# openEMSstim_02.net
KiCad netlist of a schematic drawn in EAGLE
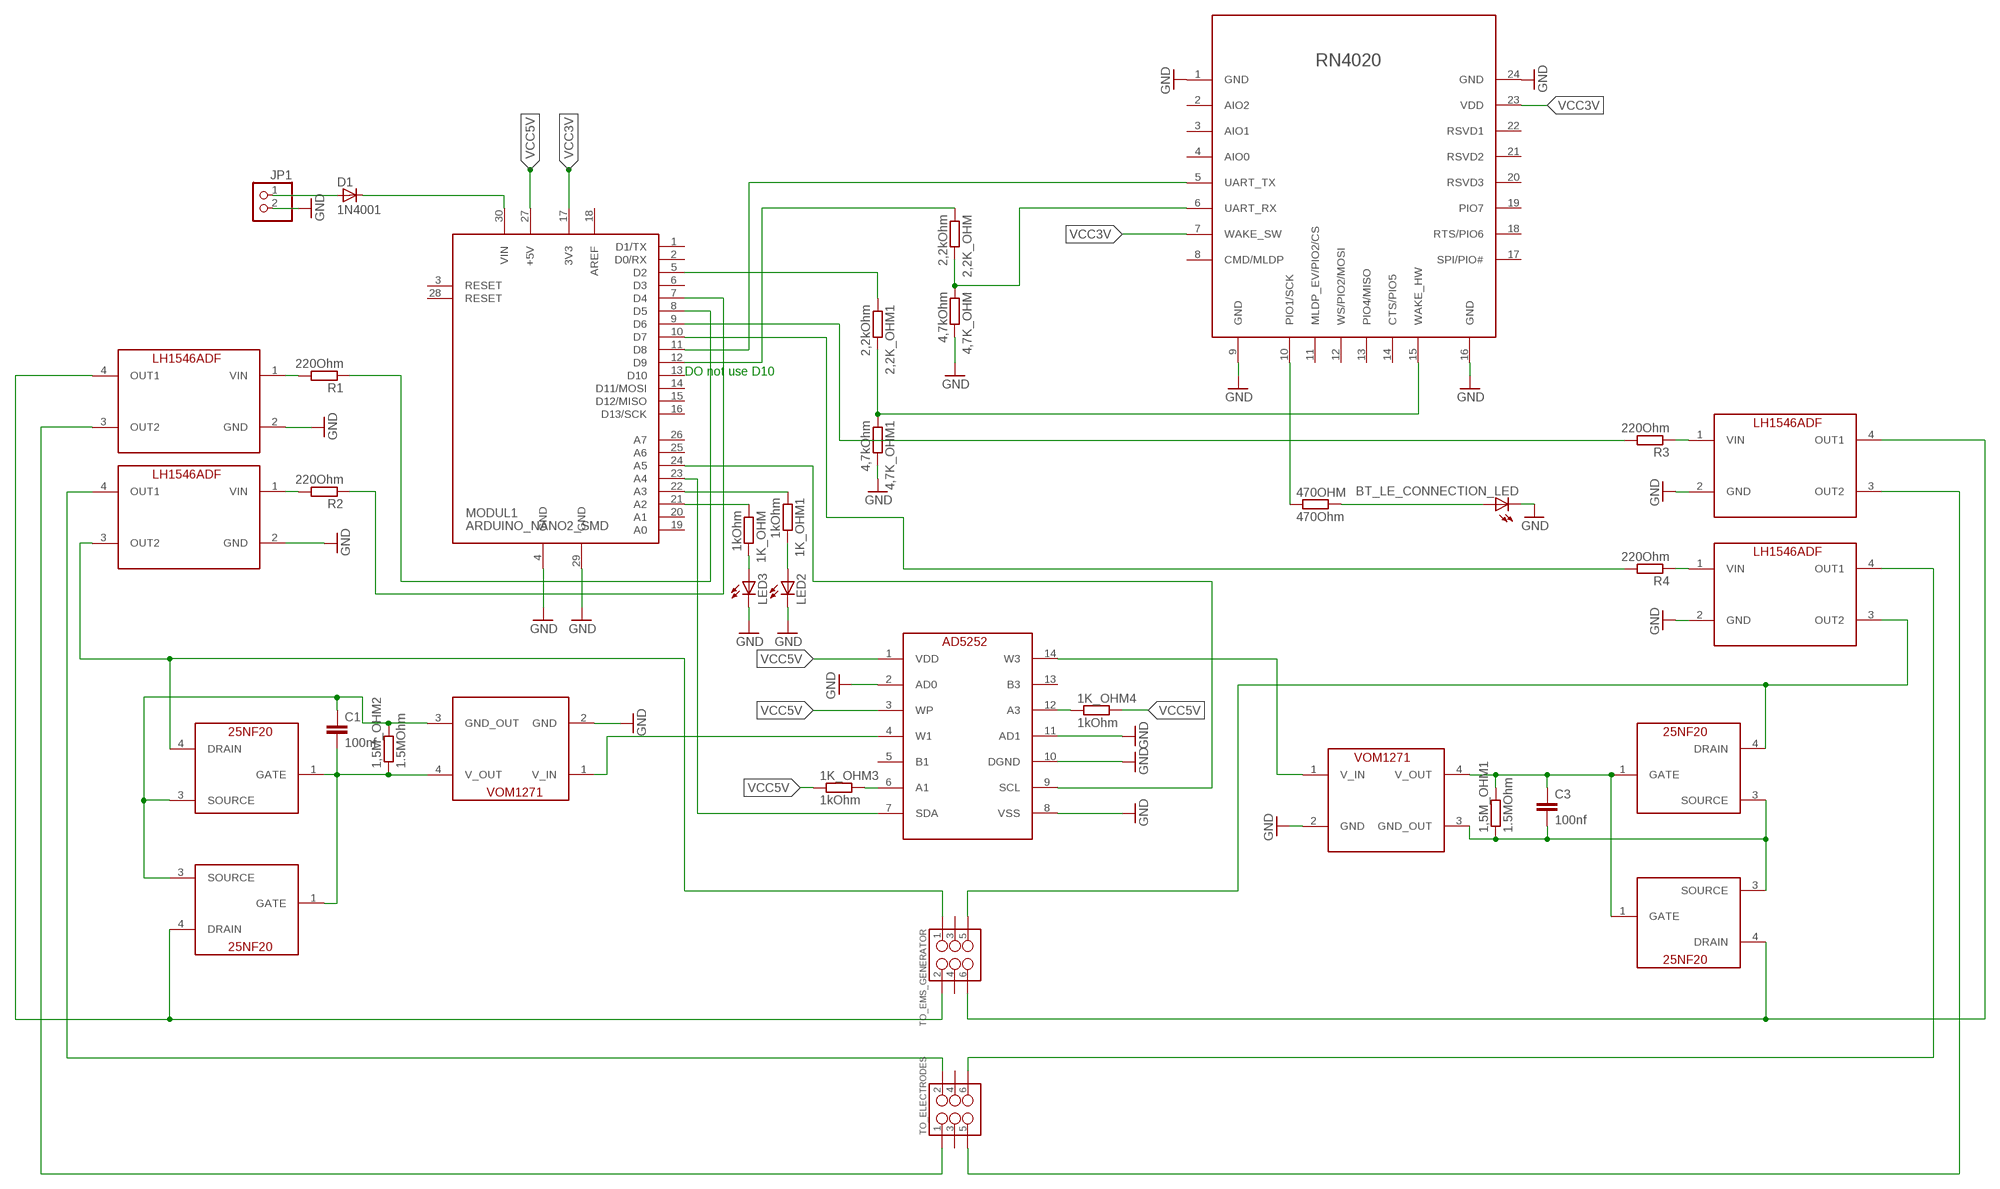
[diagram p0: schematic, sheet 1]

(export (version "E")
  (design (tool "Eeschema 10.0.6"))
  (components
    (comp (ref "1,5M_OHM1")
      (value "1.5MOhm")
      (footprint "eagle-import:R0805")
      (libsource (lib "eagle-import") (part "R-EU_R0805"))
    )
    (comp (ref "1,5M_OHM2")
      (value "1.5MOhm")
      (footprint "eagle-import:R0805")
      (libsource (lib "eagle-import") (part "R-EU_R0805"))
    )
    (comp (ref "1K_OHM")
      (value "1kOhm")
      (footprint "eagle-import:R0805")
      (libsource (lib "eagle-import") (part "R-EU_R0805"))
    )
    (comp (ref "1K_OHM1")
      (value "1kOhm")
      (footprint "eagle-import:R0805")
      (libsource (lib "eagle-import") (part "R-EU_R0805"))
    )
    (comp (ref "1K_OHM3")
      (value "1kOhm")
      (footprint "eagle-import:R0805")
      (libsource (lib "eagle-import") (part "R-EU_R0805"))
    )
    (comp (ref "1K_OHM4")
      (value "1kOhm")
      (footprint "eagle-import:R0805")
      (libsource (lib "eagle-import") (part "R-EU_R0805"))
    )
    (comp (ref "2,2K_OHM")
      (value "2,2kOhm")
      (footprint "eagle-import:R0805")
      (libsource (lib "eagle-import") (part "R-EU_R0805"))
    )
    (comp (ref "2,2K_OHM1")
      (value "2,2kOhm")
      (footprint "eagle-import:R0805")
      (libsource (lib "eagle-import") (part "R-EU_R0805"))
    )
    (comp (ref "4,7K_OHM")
      (value "4,7kOhm")
      (footprint "eagle-import:R0805")
      (libsource (lib "eagle-import") (part "R-EU_R0805"))
    )
    (comp (ref "4,7K_OHM1")
      (value "4,7kOhm")
      (footprint "eagle-import:R0805")
      (libsource (lib "eagle-import") (part "R-EU_R0805"))
    )
    (comp (ref "470OHM")
      (value "470Ohm")
      (footprint "eagle-import:R0805")
      (libsource (lib "eagle-import") (part "R-EU_R0805"))
    )
    (comp (ref "BT_LE_CONNECTION_LED")
      (value "LEDCHIPLED_0603")
      (footprint "eagle-import:CHIPLED_0603")
      (libsource (lib "eagle-import") (part "LEDCHIPLED_0603"))
    )
    (comp (ref "C1")
      (value "100nf")
      (footprint "eagle-import:0805")
      (libsource (lib "eagle-import") (part "CAP0805"))
    )
    (comp (ref "C3")
      (value "100nf")
      (footprint "eagle-import:0805")
      (libsource (lib "eagle-import") (part "CAP0805"))
    )
    (comp (ref "D1")
      (value "1N4001")
      (footprint "eagle-import:SMB")
      (libsource (lib "eagle-import") (part "D-SMB"))
    )
    (comp (ref "JP1")
      (value "PINHD-1X2")
      (footprint "eagle-import:1X02")
      (libsource (lib "eagle-import") (part "PINHD-1X2"))
    )
    (comp (ref "LED2")
      (value "LEDCHIPLED_0603")
      (footprint "eagle-import:CHIPLED_0603")
      (libsource (lib "eagle-import") (part "LEDCHIPLED_0603"))
    )
    (comp (ref "LED3")
      (value "LEDCHIPLED_0603")
      (footprint "eagle-import:CHIPLED_0603")
      (libsource (lib "eagle-import") (part "LEDCHIPLED_0603"))
    )
    (comp (ref "MODUL1")
      (value "ARDUINO_NANO2_SMD")
      (footprint "eagle-import:ARDUINO_NANO2_SMD")
      (libsource (lib "eagle-import") (part "ARDUINO_NANO2_SMD"))
    )
    (comp (ref "MOS01")
      (value "DEV")
      (footprint "eagle-import:PACK")
      (libsource (lib "eagle-import") (part "DEV"))
    )
    (comp (ref "MOS02")
      (value "DEV")
      (footprint "eagle-import:PACK")
      (libsource (lib "eagle-import") (part "DEV"))
    )
    (comp (ref "MOS03")
      (value "DEV")
      (footprint "eagle-import:PACK")
      (libsource (lib "eagle-import") (part "DEV"))
    )
    (comp (ref "MOS04")
      (value "DEV")
      (footprint "eagle-import:PACK")
      (libsource (lib "eagle-import") (part "DEV"))
    )
    (comp (ref "R1")
      (value "220Ohm")
      (footprint "eagle-import:R0805")
      (libsource (lib "eagle-import") (part "R-EU_R0805"))
    )
    (comp (ref "R2")
      (value "220Ohm")
      (footprint "eagle-import:R0805")
      (libsource (lib "eagle-import") (part "R-EU_R0805"))
    )
    (comp (ref "R3")
      (value "220Ohm")
      (footprint "eagle-import:R0805")
      (libsource (lib "eagle-import") (part "R-EU_R0805"))
    )
    (comp (ref "R4")
      (value "220Ohm")
      (footprint "eagle-import:R0805")
      (libsource (lib "eagle-import") (part "R-EU_R0805"))
    )
    (comp (ref "TO_ELECTRODES")
      (value "M03X2")
      (footprint "eagle-import:RIGHT_ANGLED_SHROUED_2X06_6PIN")
      (libsource (lib "eagle-import") (part "M03X2"))
    )
    (comp (ref "TO_EMS_GENERATOR")
      (value "M03X2")
      (footprint "eagle-import:RIGHT_ANGLED_SHROUED_2X06_6PIN")
      (libsource (lib "eagle-import") (part "M03X2"))
    )
    (comp (ref "U$5")
      (value "RN4020")
      (footprint "eagle-import:RN4020")
      (libsource (lib "eagle-import") (part "RN4020"))
    )
    (comp (ref "U$6")
      (value "AD5252")
      (footprint "eagle-import:TSSOP")
      (libsource (lib "eagle-import") (part "AD5252"))
    )
    (comp (ref "U$9")
      (value "VOM1271")
      (footprint "eagle-import:SOP04")
      (libsource (lib "eagle-import") (part "VOM1271"))
    )
    (comp (ref "U$10")
      (value "VOM1271")
      (footprint "eagle-import:SOP04")
      (libsource (lib "eagle-import") (part "VOM1271"))
    )
    (comp (ref "U$11")
      (value "LH1546ADF")
      (footprint "eagle-import:DIP04-SMD")
      (libsource (lib "eagle-import") (part "LH1546ADF"))
    )
    (comp (ref "U$12")
      (value "LH1546ADF")
      (footprint "eagle-import:DIP04-SMD")
      (libsource (lib "eagle-import") (part "LH1546ADF"))
    )
    (comp (ref "U$13")
      (value "LH1546ADF")
      (footprint "eagle-import:DIP04-SMD")
      (libsource (lib "eagle-import") (part "LH1546ADF"))
    )
    (comp (ref "U$14")
      (value "LH1546ADF")
      (footprint "eagle-import:DIP04-SMD")
      (libsource (lib "eagle-import") (part "LH1546ADF"))
    )
  )
  (nets
    (net (code "1") (name "/AREF") (class "Default")
      (node (ref "MODUL1") (pin "18") (pinfunction "AREF_18") (pintype "power_in"))
    )
    (net (code "2") (name "GND") (class "Default")
      (node (ref "4,7K_OHM") (pin "2") (pinfunction "2_2") (pintype "passive"))
      (node (ref "4,7K_OHM1") (pin "2") (pinfunction "2_2") (pintype "passive"))
      (node (ref "BT_LE_CONNECTION_LED") (pin "C") (pinfunction "C_C") (pintype "passive"))
      (node (ref "JP1") (pin "2") (pinfunction "2_2") (pintype "passive"))
      (node (ref "LED2") (pin "C") (pinfunction "C_C") (pintype "passive"))
      (node (ref "LED3") (pin "C") (pinfunction "C_C") (pintype "passive"))
      (node (ref "MODUL1") (pin "29") (pinfunction "GND_29") (pintype "power_in"))
      (node (ref "MODUL1") (pin "4") (pinfunction "GND_4") (pintype "power_in"))
      (node (ref "U$10") (pin "2") (pinfunction "GND_2") (pintype "input"))
      (node (ref "U$11") (pin "2") (pinfunction "GND_2") (pintype "bidirectional"))
      (node (ref "U$12") (pin "2") (pinfunction "GND_2") (pintype "bidirectional"))
      (node (ref "U$13") (pin "2") (pinfunction "GND_2") (pintype "bidirectional"))
      (node (ref "U$14") (pin "2") (pinfunction "GND_2") (pintype "bidirectional"))
      (node (ref "U$5") (pin "1") (pinfunction "GND_1") (pintype "power_in"))
      (node (ref "U$5") (pin "16") (pinfunction "GND_16") (pintype "power_in"))
      (node (ref "U$5") (pin "24") (pinfunction "GND_24") (pintype "power_in"))
      (node (ref "U$5") (pin "9") (pinfunction "GND_9") (pintype "power_in"))
      (node (ref "U$6") (pin "10") (pinfunction "DGND_10") (pintype "bidirectional"))
      (node (ref "U$6") (pin "11") (pinfunction "AD1_11") (pintype "bidirectional"))
      (node (ref "U$6") (pin "2") (pinfunction "AD0_2") (pintype "bidirectional"))
      (node (ref "U$6") (pin "8") (pinfunction "VSS_8") (pintype "bidirectional"))
      (node (ref "U$9") (pin "2") (pinfunction "GND_2") (pintype "input"))
    )
    (net (code "3") (name "Net-(1K_OHM-Pad2)") (class "Default")
      (node (ref "1K_OHM") (pin "2") (pinfunction "2_2") (pintype "passive"))
      (node (ref "LED3") (pin "A") (pinfunction "A_A") (pintype "passive"))
    )
    (net (code "4") (name "Net-(1K_OHM1-Pad2)") (class "Default")
      (node (ref "1K_OHM1") (pin "2") (pinfunction "2_2") (pintype "passive"))
      (node (ref "LED2") (pin "A") (pinfunction "A_A") (pintype "passive"))
    )
    (net (code "5") (name "Net-(470OHM-Pad2)") (class "Default")
      (node (ref "470OHM") (pin "2") (pinfunction "2_2") (pintype "passive"))
      (node (ref "BT_LE_CONNECTION_LED") (pin "A") (pinfunction "A_A") (pintype "passive"))
    )
    (net (code "6") (name "Net-(D1-A)") (class "Default")
      (node (ref "D1") (pin "2") (pinfunction "A_2") (pintype "passive"))
      (node (ref "JP1") (pin "1") (pinfunction "1_1") (pintype "passive"))
    )
    (net (code "7") (name "Net-(D1-C)") (class "Default")
      (node (ref "D1") (pin "1") (pinfunction "C_1") (pintype "passive"))
      (node (ref "MODUL1") (pin "30") (pinfunction "VIN_30") (pintype "power_in"))
    )
    (net (code "8") (name "Net-(MODUL1-A2)") (class "Default")
      (node (ref "1K_OHM") (pin "1") (pinfunction "1_1") (pintype "passive"))
      (node (ref "MODUL1") (pin "21") (pinfunction "A2_21") (pintype "bidirectional"))
    )
    (net (code "9") (name "Net-(MODUL1-A3)") (class "Default")
      (node (ref "1K_OHM1") (pin "1") (pinfunction "1_1") (pintype "passive"))
      (node (ref "MODUL1") (pin "22") (pinfunction "A3_22") (pintype "bidirectional"))
    )
    (net (code "10") (name "Net-(MODUL1-A4)") (class "Default")
      (node (ref "MODUL1") (pin "23") (pinfunction "A4_23") (pintype "bidirectional"))
      (node (ref "U$6") (pin "7") (pinfunction "SDA_7") (pintype "bidirectional"))
    )
    (net (code "11") (name "Net-(MODUL1-A5)") (class "Default")
      (node (ref "MODUL1") (pin "24") (pinfunction "A5_24") (pintype "bidirectional"))
      (node (ref "U$6") (pin "9") (pinfunction "SCL_9") (pintype "bidirectional"))
    )
    (net (code "12") (name "Net-(MODUL1-D2)") (class "Default")
      (node (ref "2,2K_OHM1") (pin "1") (pinfunction "1_1") (pintype "passive"))
      (node (ref "MODUL1") (pin "5") (pinfunction "D2_5") (pintype "bidirectional"))
    )
    (net (code "13") (name "Net-(MODUL1-D4)") (class "Default")
      (node (ref "MODUL1") (pin "7") (pinfunction "D4_7") (pintype "bidirectional"))
      (node (ref "R2") (pin "1") (pinfunction "1_1") (pintype "passive"))
    )
    (net (code "14") (name "Net-(MODUL1-D5)") (class "Default")
      (node (ref "MODUL1") (pin "8") (pinfunction "D5_8") (pintype "bidirectional"))
      (node (ref "R1") (pin "1") (pinfunction "1_1") (pintype "passive"))
    )
    (net (code "15") (name "Net-(MODUL1-D6)") (class "Default")
      (node (ref "MODUL1") (pin "9") (pinfunction "D6_9") (pintype "bidirectional"))
      (node (ref "R3") (pin "2") (pinfunction "2_2") (pintype "passive"))
    )
    (net (code "16") (name "Net-(MODUL1-D7)") (class "Default")
      (node (ref "MODUL1") (pin "10") (pinfunction "D7_10") (pintype "bidirectional"))
      (node (ref "R4") (pin "2") (pinfunction "2_2") (pintype "passive"))
    )
    (net (code "17") (name "Net-(MODUL1-D8)") (class "Default")
      (node (ref "MODUL1") (pin "11") (pinfunction "D8_11") (pintype "bidirectional"))
      (node (ref "U$5") (pin "5") (pinfunction "UART_TX_5") (pintype "bidirectional"))
    )
    (net (code "18") (name "Net-(MODUL1-D9)") (class "Default")
      (node (ref "2,2K_OHM") (pin "1") (pinfunction "1_1") (pintype "passive"))
      (node (ref "MODUL1") (pin "12") (pinfunction "D9_12") (pintype "bidirectional"))
    )
    (net (code "19") (name "Net-(MOS01-DRAIN)") (class "Default")
      (node (ref "MOS01") (pin "4") (pinfunction "DRAIN_4") (pintype "bidirectional"))
      (node (ref "TO_EMS_GENERATOR") (pin "1") (pinfunction "1_1") (pintype "bidirectional"))
      (node (ref "U$12") (pin "3") (pinfunction "OUT2_3") (pintype "bidirectional"))
    )
    (net (code "20") (name "Net-(MOS01-GATE)") (class "Default")
      (node (ref "1,5M_OHM2") (pin "1") (pinfunction "1_1") (pintype "passive"))
      (node (ref "C1") (pin "2") (pinfunction "2_2") (pintype "passive"))
      (node (ref "MOS01") (pin "1") (pinfunction "GATE_1") (pintype "input"))
      (node (ref "MOS02") (pin "1") (pinfunction "GATE_1") (pintype "input"))
      (node (ref "U$9") (pin "4") (pinfunction "V_OUT_4") (pintype "output"))
    )
    (net (code "21") (name "Net-(MOS01-SOURCE)") (class "Default")
      (node (ref "1,5M_OHM2") (pin "2") (pinfunction "2_2") (pintype "passive"))
      (node (ref "C1") (pin "1") (pinfunction "1_1") (pintype "passive"))
      (node (ref "MOS01") (pin "3") (pinfunction "SOURCE_3") (pintype "bidirectional"))
      (node (ref "MOS02") (pin "3") (pinfunction "SOURCE_3") (pintype "bidirectional"))
      (node (ref "U$9") (pin "3") (pinfunction "GND_OUT_3") (pintype "output"))
    )
    (net (code "22") (name "Net-(MOS02-DRAIN)") (class "Default")
      (node (ref "MOS02") (pin "4") (pinfunction "DRAIN_4") (pintype "bidirectional"))
      (node (ref "TO_EMS_GENERATOR") (pin "2") (pinfunction "2_2") (pintype "bidirectional"))
      (node (ref "U$11") (pin "4") (pinfunction "OUT1_4") (pintype "bidirectional"))
    )
    (net (code "23") (name "Net-(MOS03-DRAIN)") (class "Default")
      (node (ref "MOS03") (pin "4") (pinfunction "DRAIN_4") (pintype "bidirectional"))
      (node (ref "TO_EMS_GENERATOR") (pin "5") (pinfunction "5_5") (pintype "bidirectional"))
      (node (ref "U$14") (pin "3") (pinfunction "OUT2_3") (pintype "bidirectional"))
    )
    (net (code "24") (name "Net-(MOS03-GATE)") (class "Default")
      (node (ref "1,5M_OHM1") (pin "2") (pinfunction "2_2") (pintype "passive"))
      (node (ref "C3") (pin "1") (pinfunction "1_1") (pintype "passive"))
      (node (ref "MOS03") (pin "1") (pinfunction "GATE_1") (pintype "input"))
      (node (ref "MOS04") (pin "1") (pinfunction "GATE_1") (pintype "input"))
      (node (ref "U$10") (pin "4") (pinfunction "V_OUT_4") (pintype "output"))
    )
    (net (code "25") (name "Net-(MOS03-SOURCE)") (class "Default")
      (node (ref "1,5M_OHM1") (pin "1") (pinfunction "1_1") (pintype "passive"))
      (node (ref "C3") (pin "2") (pinfunction "2_2") (pintype "passive"))
      (node (ref "MOS03") (pin "3") (pinfunction "SOURCE_3") (pintype "bidirectional"))
      (node (ref "MOS04") (pin "3") (pinfunction "SOURCE_3") (pintype "bidirectional"))
      (node (ref "U$10") (pin "3") (pinfunction "GND_OUT_3") (pintype "output"))
    )
    (net (code "26") (name "Net-(MOS04-DRAIN)") (class "Default")
      (node (ref "MOS04") (pin "4") (pinfunction "DRAIN_4") (pintype "bidirectional"))
      (node (ref "TO_EMS_GENERATOR") (pin "6") (pinfunction "6_6") (pintype "bidirectional"))
      (node (ref "U$13") (pin "4") (pinfunction "OUT1_4") (pintype "bidirectional"))
    )
    (net (code "27") (name "Net-(U$5-PIO1{slash}SCK)") (class "Default")
      (node (ref "470OHM") (pin "1") (pinfunction "1_1") (pintype "passive"))
      (node (ref "U$5") (pin "10") (pinfunction "PIO1/SCK_10") (pintype "bidirectional"))
    )
    (net (code "28") (name "Net-(U$5-UART_RX)") (class "Default")
      (node (ref "2,2K_OHM") (pin "2") (pinfunction "2_2") (pintype "passive"))
      (node (ref "4,7K_OHM") (pin "1") (pinfunction "1_1") (pintype "passive"))
      (node (ref "U$5") (pin "6") (pinfunction "UART_RX_6") (pintype "bidirectional"))
    )
    (net (code "29") (name "Net-(U$5-WAKE_HW)") (class "Default")
      (node (ref "2,2K_OHM1") (pin "2") (pinfunction "2_2") (pintype "passive"))
      (node (ref "4,7K_OHM1") (pin "1") (pinfunction "1_1") (pintype "passive"))
      (node (ref "U$5") (pin "15") (pinfunction "WAKE_HW_15") (pintype "bidirectional"))
    )
    (net (code "30") (name "Net-(U$6-A1)") (class "Default")
      (node (ref "1K_OHM3") (pin "2") (pinfunction "2_2") (pintype "passive"))
      (node (ref "U$6") (pin "6") (pinfunction "A1_6") (pintype "bidirectional"))
    )
    (net (code "31") (name "Net-(U$6-A3)") (class "Default")
      (node (ref "1K_OHM4") (pin "1") (pinfunction "1_1") (pintype "passive"))
      (node (ref "U$6") (pin "12") (pinfunction "A3_12") (pintype "bidirectional"))
    )
    (net (code "32") (name "Net-(U$6-W1)") (class "Default")
      (node (ref "U$6") (pin "4") (pinfunction "W1_4") (pintype "bidirectional"))
      (node (ref "U$9") (pin "1") (pinfunction "V_IN_1") (pintype "input"))
    )
    (net (code "33") (name "Net-(U$10-V_IN)") (class "Default")
      (node (ref "U$10") (pin "1") (pinfunction "V_IN_1") (pintype "input"))
      (node (ref "U$6") (pin "14") (pinfunction "W3_14") (pintype "bidirectional"))
    )
    (net (code "34") (name "Net-(U$11-OUT2)") (class "Default")
      (node (ref "TO_ELECTRODES") (pin "1") (pinfunction "1_1") (pintype "bidirectional"))
      (node (ref "U$11") (pin "3") (pinfunction "OUT2_3") (pintype "bidirectional"))
    )
    (net (code "35") (name "Net-(U$11-VIN)") (class "Default")
      (node (ref "R1") (pin "2") (pinfunction "2_2") (pintype "passive"))
      (node (ref "U$11") (pin "1") (pinfunction "VIN_1") (pintype "bidirectional"))
    )
    (net (code "36") (name "Net-(U$12-OUT1)") (class "Default")
      (node (ref "TO_ELECTRODES") (pin "2") (pinfunction "2_2") (pintype "bidirectional"))
      (node (ref "U$12") (pin "4") (pinfunction "OUT1_4") (pintype "bidirectional"))
    )
    (net (code "37") (name "Net-(U$12-VIN)") (class "Default")
      (node (ref "R2") (pin "2") (pinfunction "2_2") (pintype "passive"))
      (node (ref "U$12") (pin "1") (pinfunction "VIN_1") (pintype "bidirectional"))
    )
    (net (code "38") (name "Net-(U$13-OUT2)") (class "Default")
      (node (ref "TO_ELECTRODES") (pin "5") (pinfunction "5_5") (pintype "bidirectional"))
      (node (ref "U$13") (pin "3") (pinfunction "OUT2_3") (pintype "bidirectional"))
    )
    (net (code "39") (name "Net-(U$13-VIN)") (class "Default")
      (node (ref "R3") (pin "1") (pinfunction "1_1") (pintype "passive"))
      (node (ref "U$13") (pin "1") (pinfunction "VIN_1") (pintype "bidirectional"))
    )
    (net (code "40") (name "Net-(U$14-OUT1)") (class "Default")
      (node (ref "TO_ELECTRODES") (pin "6") (pinfunction "6_6") (pintype "bidirectional"))
      (node (ref "U$14") (pin "4") (pinfunction "OUT1_4") (pintype "bidirectional"))
    )
    (net (code "41") (name "Net-(U$14-VIN)") (class "Default")
      (node (ref "R4") (pin "1") (pinfunction "1_1") (pintype "passive"))
      (node (ref "U$14") (pin "1") (pinfunction "VIN_1") (pintype "bidirectional"))
    )
    (net (code "42") (name "VCC3V") (class "Default")
      (node (ref "MODUL1") (pin "17") (pinfunction "3V3_17") (pintype "power_in"))
      (node (ref "U$5") (pin "23") (pinfunction "VDD_23") (pintype "power_in"))
      (node (ref "U$5") (pin "7") (pinfunction "WAKE_SW_7") (pintype "bidirectional"))
    )
    (net (code "43") (name "VCC5V") (class "Default")
      (node (ref "1K_OHM3") (pin "1") (pinfunction "1_1") (pintype "passive"))
      (node (ref "1K_OHM4") (pin "2") (pinfunction "2_2") (pintype "passive"))
      (node (ref "MODUL1") (pin "27") (pinfunction "+5V_27") (pintype "power_in"))
      (node (ref "U$6") (pin "1") (pinfunction "VDD_1") (pintype "bidirectional"))
      (node (ref "U$6") (pin "3") (pinfunction "WP_3") (pintype "bidirectional"))
    )
    (net (code "44") (name "unconnected-(MODUL1-A0-Pad19)") (class "Default")
      (node (ref "MODUL1") (pin "19") (pinfunction "A0_19") (pintype "bidirectional"))
    )
    (net (code "45") (name "unconnected-(MODUL1-A1-Pad20)") (class "Default")
      (node (ref "MODUL1") (pin "20") (pinfunction "A1_20") (pintype "bidirectional"))
    )
    (net (code "46") (name "unconnected-(MODUL1-A6-Pad25)") (class "Default")
      (node (ref "MODUL1") (pin "25") (pinfunction "A6_25") (pintype "bidirectional"))
    )
    (net (code "47") (name "unconnected-(MODUL1-A7-Pad26)") (class "Default")
      (node (ref "MODUL1") (pin "26") (pinfunction "A7_26") (pintype "bidirectional"))
    )
    (net (code "48") (name "unconnected-(MODUL1-D0{slash}RX-Pad2)") (class "Default")
      (node (ref "MODUL1") (pin "2") (pinfunction "D0/RX_2") (pintype "bidirectional"))
    )
    (net (code "49") (name "unconnected-(MODUL1-D1{slash}TX-Pad1)") (class "Default")
      (node (ref "MODUL1") (pin "1") (pinfunction "D1/TX_1") (pintype "bidirectional"))
    )
    (net (code "50") (name "unconnected-(MODUL1-D3-Pad6)") (class "Default")
      (node (ref "MODUL1") (pin "6") (pinfunction "D3_6") (pintype "bidirectional"))
    )
    (net (code "51") (name "unconnected-(MODUL1-D10-Pad13)") (class "Default")
      (node (ref "MODUL1") (pin "13") (pinfunction "D10_13") (pintype "bidirectional"))
    )
    (net (code "52") (name "unconnected-(MODUL1-D11{slash}MOSI-Pad14)") (class "Default")
      (node (ref "MODUL1") (pin "14") (pinfunction "D11/MOSI_14") (pintype "bidirectional"))
    )
    (net (code "53") (name "unconnected-(MODUL1-D12{slash}MISO-Pad15)") (class "Default")
      (node (ref "MODUL1") (pin "15") (pinfunction "D12/MISO_15") (pintype "bidirectional"))
    )
    (net (code "54") (name "unconnected-(MODUL1-D13{slash}SCK-Pad16)") (class "Default")
      (node (ref "MODUL1") (pin "16") (pinfunction "D13/SCK_16") (pintype "bidirectional"))
    )
    (net (code "55") (name "unconnected-(MODUL1-RESET-Pad3)") (class "Default")
      (node (ref "MODUL1") (pin "3") (pinfunction "RESET_3") (pintype "bidirectional"))
    )
    (net (code "56") (name "unconnected-(MODUL1-RESET-Pad28)") (class "Default")
      (node (ref "MODUL1") (pin "28") (pinfunction "RESET_28") (pintype "bidirectional"))
    )
    (net (code "57") (name "unconnected-(TO_ELECTRODES-Pad3)") (class "Default")
      (node (ref "TO_ELECTRODES") (pin "3") (pinfunction "3_3") (pintype "bidirectional"))
    )
    (net (code "58") (name "unconnected-(TO_ELECTRODES-Pad4)") (class "Default")
      (node (ref "TO_ELECTRODES") (pin "4") (pinfunction "4_4") (pintype "bidirectional"))
    )
    (net (code "59") (name "unconnected-(TO_EMS_GENERATOR-Pad3)") (class "Default")
      (node (ref "TO_EMS_GENERATOR") (pin "3") (pinfunction "3_3") (pintype "bidirectional"))
    )
    (net (code "60") (name "unconnected-(TO_EMS_GENERATOR-Pad4)") (class "Default")
      (node (ref "TO_EMS_GENERATOR") (pin "4") (pinfunction "4_4") (pintype "bidirectional"))
    )
    (net (code "61") (name "unconnected-(U$5-AIO0-Pad4)") (class "Default")
      (node (ref "U$5") (pin "4") (pinfunction "AIO0_4") (pintype "bidirectional"))
    )
    (net (code "62") (name "unconnected-(U$5-AIO1-Pad3)") (class "Default")
      (node (ref "U$5") (pin "3") (pinfunction "AIO1_3") (pintype "bidirectional"))
    )
    (net (code "63") (name "unconnected-(U$5-AIO2-Pad2)") (class "Default")
      (node (ref "U$5") (pin "2") (pinfunction "AIO2_2") (pintype "bidirectional"))
    )
    (net (code "64") (name "unconnected-(U$5-CMD{slash}MLDP-Pad8)") (class "Default")
      (node (ref "U$5") (pin "8") (pinfunction "CMD/MLDP_8") (pintype "bidirectional"))
    )
    (net (code "65") (name "unconnected-(U$5-CTS{slash}PIO5-Pad14)") (class "Default")
      (node (ref "U$5") (pin "14") (pinfunction "CTS/PIO5_14") (pintype "bidirectional"))
    )
    (net (code "66") (name "unconnected-(U$5-MLDP_EV{slash}PIO2{slash}CS-Pad11)") (class "Default")
      (node (ref "U$5") (pin "11") (pinfunction "MLDP_EV/PIO2/CS_11") (pintype "bidirectional"))
    )
    (net (code "67") (name "unconnected-(U$5-PIO4{slash}MISO-Pad13)") (class "Default")
      (node (ref "U$5") (pin "13") (pinfunction "PIO4/MISO_13") (pintype "bidirectional"))
    )
    (net (code "68") (name "unconnected-(U$5-PIO7-Pad19)") (class "Default")
      (node (ref "U$5") (pin "19") (pinfunction "PIO7_19") (pintype "bidirectional"))
    )
    (net (code "69") (name "unconnected-(U$5-RSVD1-Pad22)") (class "Default")
      (node (ref "U$5") (pin "22") (pinfunction "RSVD1_22") (pintype "bidirectional"))
    )
    (net (code "70") (name "unconnected-(U$5-RSVD2-Pad21)") (class "Default")
      (node (ref "U$5") (pin "21") (pinfunction "RSVD2_21") (pintype "bidirectional"))
    )
    (net (code "71") (name "unconnected-(U$5-RSVD3-Pad20)") (class "Default")
      (node (ref "U$5") (pin "20") (pinfunction "RSVD3_20") (pintype "bidirectional"))
    )
    (net (code "72") (name "unconnected-(U$5-RTS{slash}PIO6-Pad18)") (class "Default")
      (node (ref "U$5") (pin "18") (pinfunction "RTS/PIO6_18") (pintype "bidirectional"))
    )
    (net (code "73") (name "unconnected-(U$5-SPI{slash}PIO#-Pad17)") (class "Default")
      (node (ref "U$5") (pin "17") (pinfunction "SPI/PIO#_17") (pintype "bidirectional"))
    )
    (net (code "74") (name "unconnected-(U$5-WS{slash}PIO2{slash}MOSI-Pad12)") (class "Default")
      (node (ref "U$5") (pin "12") (pinfunction "WS/PIO2/MOSI_12") (pintype "bidirectional"))
    )
    (net (code "75") (name "unconnected-(U$6-B1-Pad5)") (class "Default")
      (node (ref "U$6") (pin "5") (pinfunction "B1_5") (pintype "bidirectional"))
    )
    (net (code "76") (name "unconnected-(U$6-B3-Pad13)") (class "Default")
      (node (ref "U$6") (pin "13") (pinfunction "B3_13") (pintype "bidirectional"))
    )
  )
)
